# Qwiic_I2C_Capacitor.net
KiCad netlist of a schematic drawn in EAGLE
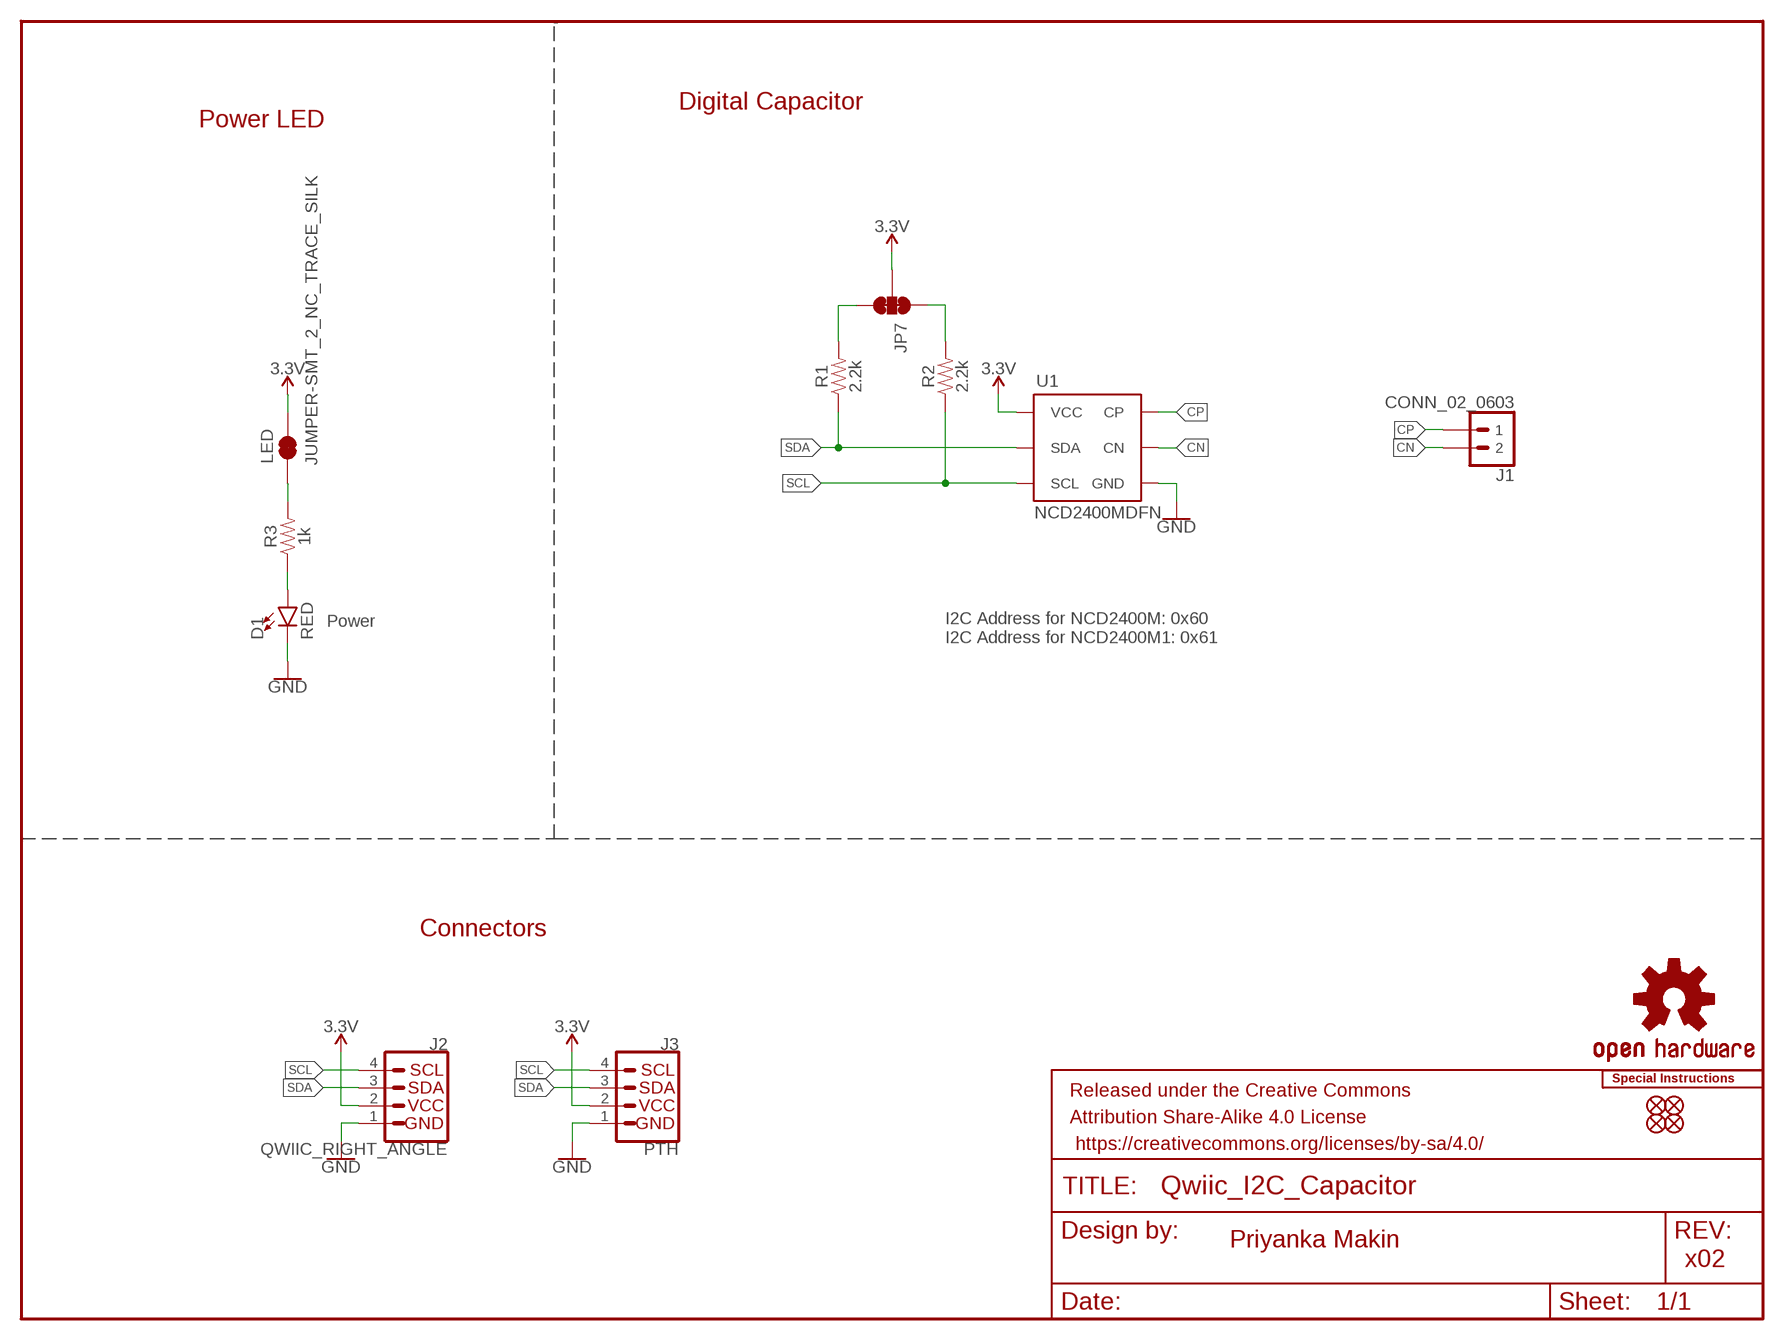
[diagram p0: schematic, sheet 1]

(export (version "E")
  (design (tool "Eeschema 10.0.6"))
  (components
    (comp (ref "D1")
      (value "RED")
      (footprint "eagle-import:LED-0603")
      (libsource (lib "eagle-import") (part "LED-RED0603"))
    )
    (comp (ref "FRAME1")
      (value "FRAME-LETTER")
      (footprint "eagle-import:CREATIVE_COMMONS")
      (libsource (lib "eagle-import") (part "FRAME-LETTER"))
    )
    (comp (ref "J1")
      (value "CONN_02_0603")
      (footprint "eagle-import:0603_CASTELLATED")
      (libsource (lib "eagle-import") (part "CONN_02_0603"))
    )
    (comp (ref "J2")
      (value "QWIIC_RIGHT_ANGLE")
      (footprint "eagle-import:JST04_1MM_RA")
      (libsource (lib "eagle-import") (part "QWIIC_CONNECTORJS-1MM"))
    )
    (comp (ref "J3")
      (value "PTH")
      (footprint "eagle-import:1X04_NO_SILK")
      (libsource (lib "eagle-import") (part "I2C_STANDARD_NO_SILK"))
    )
    (comp (ref "JP1")
      (value "FIDUCIAL0.2MM")
      (footprint "eagle-import:FIDUCIAL-0.2MM")
      (libsource (lib "eagle-import") (part "FIDUCIAL0.2MM"))
    )
    (comp (ref "JP2")
      (value "FIDUCIAL0.2MM")
      (footprint "eagle-import:FIDUCIAL-0.2MM")
      (libsource (lib "eagle-import") (part "FIDUCIAL0.2MM"))
    )
    (comp (ref "JP5")
      (value "FIDUCIAL0.2MM")
      (footprint "eagle-import:FIDUCIAL-0.2MM")
      (libsource (lib "eagle-import") (part "FIDUCIAL0.2MM"))
    )
    (comp (ref "JP6")
      (value "FIDUCIAL0.2MM")
      (footprint "eagle-import:FIDUCIAL-0.2MM")
      (libsource (lib "eagle-import") (part "FIDUCIAL0.2MM"))
    )
    (comp (ref "JP7")
      (value "JUMPER-SMT_3_2-NC_TRACE_SILK")
      (footprint "eagle-import:SMT-JUMPER_3_2-NC_TRACE_SILK")
      (libsource (lib "eagle-import") (part "JUMPER-SMT_3_2-NC_TRACE_SILK"))
    )
    (comp (ref "LED")
      (value "JUMPER-SMT_2_NC_TRACE_SILK")
      (footprint "eagle-import:SMT-JUMPER_2_NC_TRACE_SILK")
      (libsource (lib "eagle-import") (part "JUMPER-SMT_2_NC_TRACE_SILK"))
    )
    (comp (ref "LOGO1")
      (value "OSHW-LOGOMINI")
      (footprint "eagle-import:OSHW-LOGO-MINI")
      (libsource (lib "eagle-import") (part "OSHW-LOGOMINI"))
    )
    (comp (ref "LOGO2")
      (value "SPECIAL_INSTRUCTIONS-ORDERING")
      (footprint "eagle-import:ORDERING_INSTRUCTIONS")
      (libsource (lib "eagle-import") (part "SPECIAL_INSTRUCTIONS-ORDERING"))
    )
    (comp (ref "R1")
      (value "2.2k")
      (footprint "eagle-import:0603")
      (libsource (lib "eagle-import") (part "2.2KOHM-0603-1/10W-1%"))
    )
    (comp (ref "R2")
      (value "2.2k")
      (footprint "eagle-import:0603")
      (libsource (lib "eagle-import") (part "2.2KOHM-0603-1/10W-1%"))
    )
    (comp (ref "R3")
      (value "1k")
      (footprint "eagle-import:0603")
      (libsource (lib "eagle-import") (part "1KOHM-0603-1/10W-1%"))
    )
    (comp (ref "U1")
      (value "NCD2400MDFN")
      (footprint "eagle-import:DFN6")
      (libsource (lib "eagle-import") (part "NCD2400MDFN"))
    )
  )
  (nets
    (net (code "1") (name "3.3V") (class "Default")
      (node (ref "J2") (pin "2") (pinfunction "2_2") (pintype "power_in"))
      (node (ref "J3") (pin "2") (pinfunction "VCC_2") (pintype "power_in"))
      (node (ref "JP7") (pin "2") (pinfunction "2_2") (pintype "passive"))
      (node (ref "LED") (pin "2") (pinfunction "2_2") (pintype "passive"))
      (node (ref "U1") (pin "4") (pinfunction "VCC_4") (pintype "power_in"))
    )
    (net (code "2") (name "CN") (class "Default")
      (node (ref "J1") (pin "2") (pinfunction "2_2") (pintype "passive"))
      (node (ref "U1") (pin "3") (pinfunction "CN_3") (pintype "output"))
    )
    (net (code "3") (name "CP") (class "Default")
      (node (ref "J1") (pin "1") (pinfunction "1_1") (pintype "passive"))
      (node (ref "U1") (pin "2") (pinfunction "CP_2") (pintype "output"))
    )
    (net (code "4") (name "GND") (class "Default")
      (node (ref "D1") (pin "C") (pinfunction "C_C") (pintype "passive"))
      (node (ref "J2") (pin "1") (pinfunction "1_1") (pintype "power_in"))
      (node (ref "J3") (pin "1") (pinfunction "GND_1") (pintype "power_in"))
      (node (ref "U1") (pin "5") (pinfunction "GND_5") (pintype "power_in"))
    )
    (net (code "5") (name "Net-(D1-PadA)") (class "Default")
      (node (ref "D1") (pin "A") (pinfunction "A_A") (pintype "passive"))
      (node (ref "R3") (pin "1") (pinfunction "1_1") (pintype "passive"))
    )
    (net (code "6") (name "Net-(JP7-Pad1)") (class "Default")
      (node (ref "JP7") (pin "1") (pinfunction "1_1") (pintype "passive"))
      (node (ref "R2") (pin "2") (pinfunction "2_2") (pintype "passive"))
    )
    (net (code "7") (name "Net-(JP7-Pad3)") (class "Default")
      (node (ref "JP7") (pin "3") (pinfunction "3_3") (pintype "passive"))
      (node (ref "R1") (pin "2") (pinfunction "2_2") (pintype "passive"))
    )
    (net (code "8") (name "Net-(LED-Pad1)") (class "Default")
      (node (ref "LED") (pin "1") (pinfunction "1_1") (pintype "passive"))
      (node (ref "R3") (pin "2") (pinfunction "2_2") (pintype "passive"))
    )
    (net (code "9") (name "SCL") (class "Default")
      (node (ref "J2") (pin "4") (pinfunction "4_4") (pintype "passive"))
      (node (ref "J3") (pin "4") (pinfunction "SCL_4") (pintype "passive"))
      (node (ref "R2") (pin "1") (pinfunction "1_1") (pintype "passive"))
      (node (ref "U1") (pin "6") (pinfunction "SCL_6") (pintype "bidirectional"))
    )
    (net (code "10") (name "SDA") (class "Default")
      (node (ref "J2") (pin "3") (pinfunction "3_3") (pintype "passive"))
      (node (ref "J3") (pin "3") (pinfunction "SDA_3") (pintype "passive"))
      (node (ref "R1") (pin "1") (pinfunction "1_1") (pintype "passive"))
      (node (ref "U1") (pin "1") (pinfunction "SDA_1") (pintype "bidirectional"))
    )
  )
)
